# Fan_Controller.net
KiCad netlist of a schematic drawn in Altium Designer
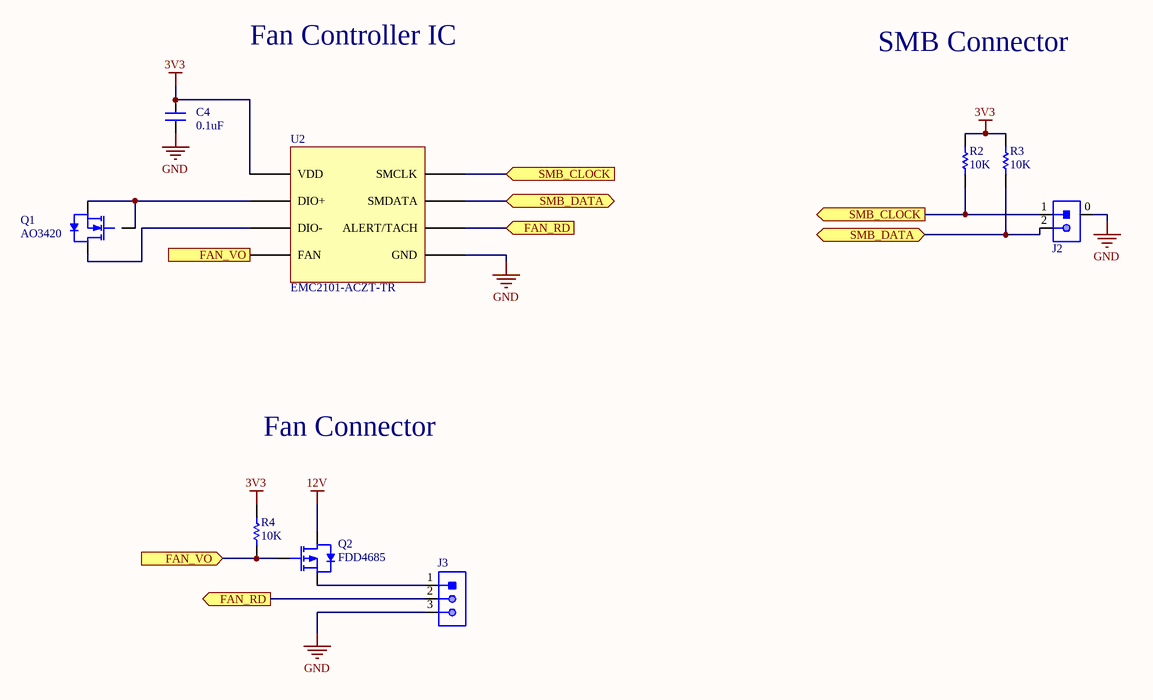
[diagram p0: Fan Controller.SchDoc]

(export (version "E")
  (design (tool "Eeschema 10.0.6"))
  (components
    (comp (ref "C4")
      (value "0.1uF")
      (footprint "CAPC2012X140N")
      (description "CAP CER 0.1UF 50V X7R 0805")
      (fields (field (name "TOLERANCE") "10%") (field (name "Comment") "CAP_0.1uF_50V_0805"))
      (libsource (lib "UWRT_Schematic_Library_2020") (part "CAP_0.1uF_50V_0805"))
    )
    (comp (ref "J2")
      (value "CON_2M_SM4")
      (footprint "JST-B2B-SM4-TB")
      (description "CONN HEADER SMD 2POS 2MM")
      (libsource (lib "UWRT_Schematic_Library_2020") (part "CON_2M_SM4"))
    )
    (comp (ref "J3")
      (value "CON_3M_TERM")
      (footprint "3 PIN TERM")
      (description "TERM BLK 3POS SIDE ENTRY 5MM PCB")
      (libsource (lib "UWRT_Schematic_Library_2020") (part "CON_3M_TERM"))
    )
    (comp (ref "Q1")
      (value "NMOS_20V_6A")
      (footprint "NMOS_SOT23-3")
      (description "MOSFET N-CH 20V 6A SOT23")
      (fields (field (name "MANUFACTURER PART NUMBER 1") "AO3420"))
      (libsource (lib "UWRT_Schematic_Library_2020") (part "NMOS_20V_6A"))
    )
    (comp (ref "Q2")
      (value "PMOS_40V_8.4A")
      (footprint "D-PAK")
      (description "MOSFET P-CH 40V 8.4A D-PAK")
      (fields (field (name "MANUFACTURER PART NUMBER 1") "FDD4685"))
      (libsource (lib "UWRT_Schematic_Library_2020") (part "PMOS_40V_8.4A"))
    )
    (comp (ref "R2")
      (value "10K")
      (footprint "RESC0603(1608)_N")
      (description "RES SMD 10K OHM 5% 1/10W 0603")
      (fields (field (name "TOLERANCE") "5%") (field (name "Comment") "RES_10K_0603"))
      (libsource (lib "UWRT_Schematic_Library_2020") (part "RES_10K_0603"))
    )
    (comp (ref "R3")
      (value "10K")
      (footprint "RESC0603(1608)_N")
      (description "RES SMD 10K OHM 5% 1/10W 0603")
      (fields (field (name "TOLERANCE") "5%") (field (name "Comment") "RES_10K_0603"))
      (libsource (lib "UWRT_Schematic_Library_2020") (part "RES_10K_0603"))
    )
    (comp (ref "R4")
      (value "10K")
      (footprint "RESC0603(1608)_N")
      (description "RES SMD 10K OHM 5% 1/10W 0603")
      (fields (field (name "TOLERANCE") "5%") (field (name "Comment") "RES_10K_0603"))
      (libsource (lib "UWRT_Schematic_Library_2020") (part "RES_10K_0603"))
    )
    (comp (ref "U2")
      (value "EMC2101-ACZT-TR")
      (footprint "SOIC-8_SG")
      (description "SMBUS FAN CONTROL WITH TEMP MONITORING")
      (libsource (lib "UWRT_Schematic_Library_2020") (part "EMC2101-ACZT-TR"))
    )
  )
  (nets
    (net (code "1") (name "/FAN_RD") (class "Default")
      (node (ref "J3") (pin "2") (pinfunction "2_2") (pintype "passive"))
      (node (ref "U2") (pin "6") (pinfunction "ALERT/TACH_6") (pintype "passive"))
    )
    (net (code "2") (name "/FAN_VO") (class "Default")
      (node (ref "Q2") (pin "2") (pinfunction "Gate_2") (pintype "passive"))
      (node (ref "R4") (pin "2") (pinfunction "2_2") (pintype "passive"))
      (node (ref "U2") (pin "4") (pinfunction "FAN_4") (pintype "passive"))
    )
    (net (code "3") (name "/SMB_CLOCK") (class "Default")
      (node (ref "J2") (pin "1") (pinfunction "1_1") (pintype "passive"))
      (node (ref "R2") (pin "1") (pinfunction "1_1") (pintype "passive"))
      (node (ref "U2") (pin "8") (pinfunction "SMCLK_8") (pintype "passive"))
    )
    (net (code "4") (name "/SMB_DATA") (class "Default")
      (node (ref "J2") (pin "2") (pinfunction "2_2") (pintype "passive"))
      (node (ref "R3") (pin "1") (pinfunction "1_1") (pintype "passive"))
      (node (ref "U2") (pin "7") (pinfunction "SMDATA_7") (pintype "passive"))
    )
    (net (code "5") (name "3V3") (class "Default")
      (node (ref "C4") (pin "2") (pinfunction "2_2") (pintype "passive"))
      (node (ref "R2") (pin "2") (pinfunction "2_2") (pintype "passive"))
      (node (ref "R3") (pin "2") (pinfunction "2_2") (pintype "passive"))
      (node (ref "R4") (pin "1") (pinfunction "1_1") (pintype "passive"))
      (node (ref "U2") (pin "1") (pinfunction "VDD_1") (pintype "passive"))
    )
    (net (code "6") (name "12V") (class "Default")
      (node (ref "Q2") (pin "1") (pinfunction "Drain_1") (pintype "passive"))
    )
    (net (code "7") (name "GND") (class "Default")
      (node (ref "C4") (pin "1") (pinfunction "1_1") (pintype "passive"))
      (node (ref "J2") (pin "0") (pinfunction "0_0") (pintype "passive"))
      (node (ref "J3") (pin "3") (pinfunction "3_3") (pintype "passive"))
      (node (ref "U2") (pin "5") (pinfunction "GND_5") (pintype "passive"))
    )
    (net (code "8") (name "Net-(Q1-D)") (class "Default")
      (node (ref "Q1") (pin "3") (pinfunction "D_3") (pintype "passive"))
      (node (ref "U2") (pin "3") (pinfunction "DIO-_3") (pintype "passive"))
    )
    (net (code "9") (name "Net-(Q1-G)") (class "Default")
      (node (ref "Q1") (pin "1") (pinfunction "G_1") (pintype "passive"))
      (node (ref "Q1") (pin "2") (pinfunction "S_2") (pintype "passive"))
      (node (ref "U2") (pin "2") (pinfunction "DIO+_2") (pintype "passive"))
    )
    (net (code "10") (name "Net-(Q2-Source)") (class "Default")
      (node (ref "J3") (pin "1") (pinfunction "1_1") (pintype "passive"))
      (node (ref "Q2") (pin "3") (pinfunction "Source_3") (pintype "passive"))
    )
  )
)
